# BM43112DC02_PIJIAKUN_SCH.net
KiCad netlist of a schematic drawn in Altium Designer
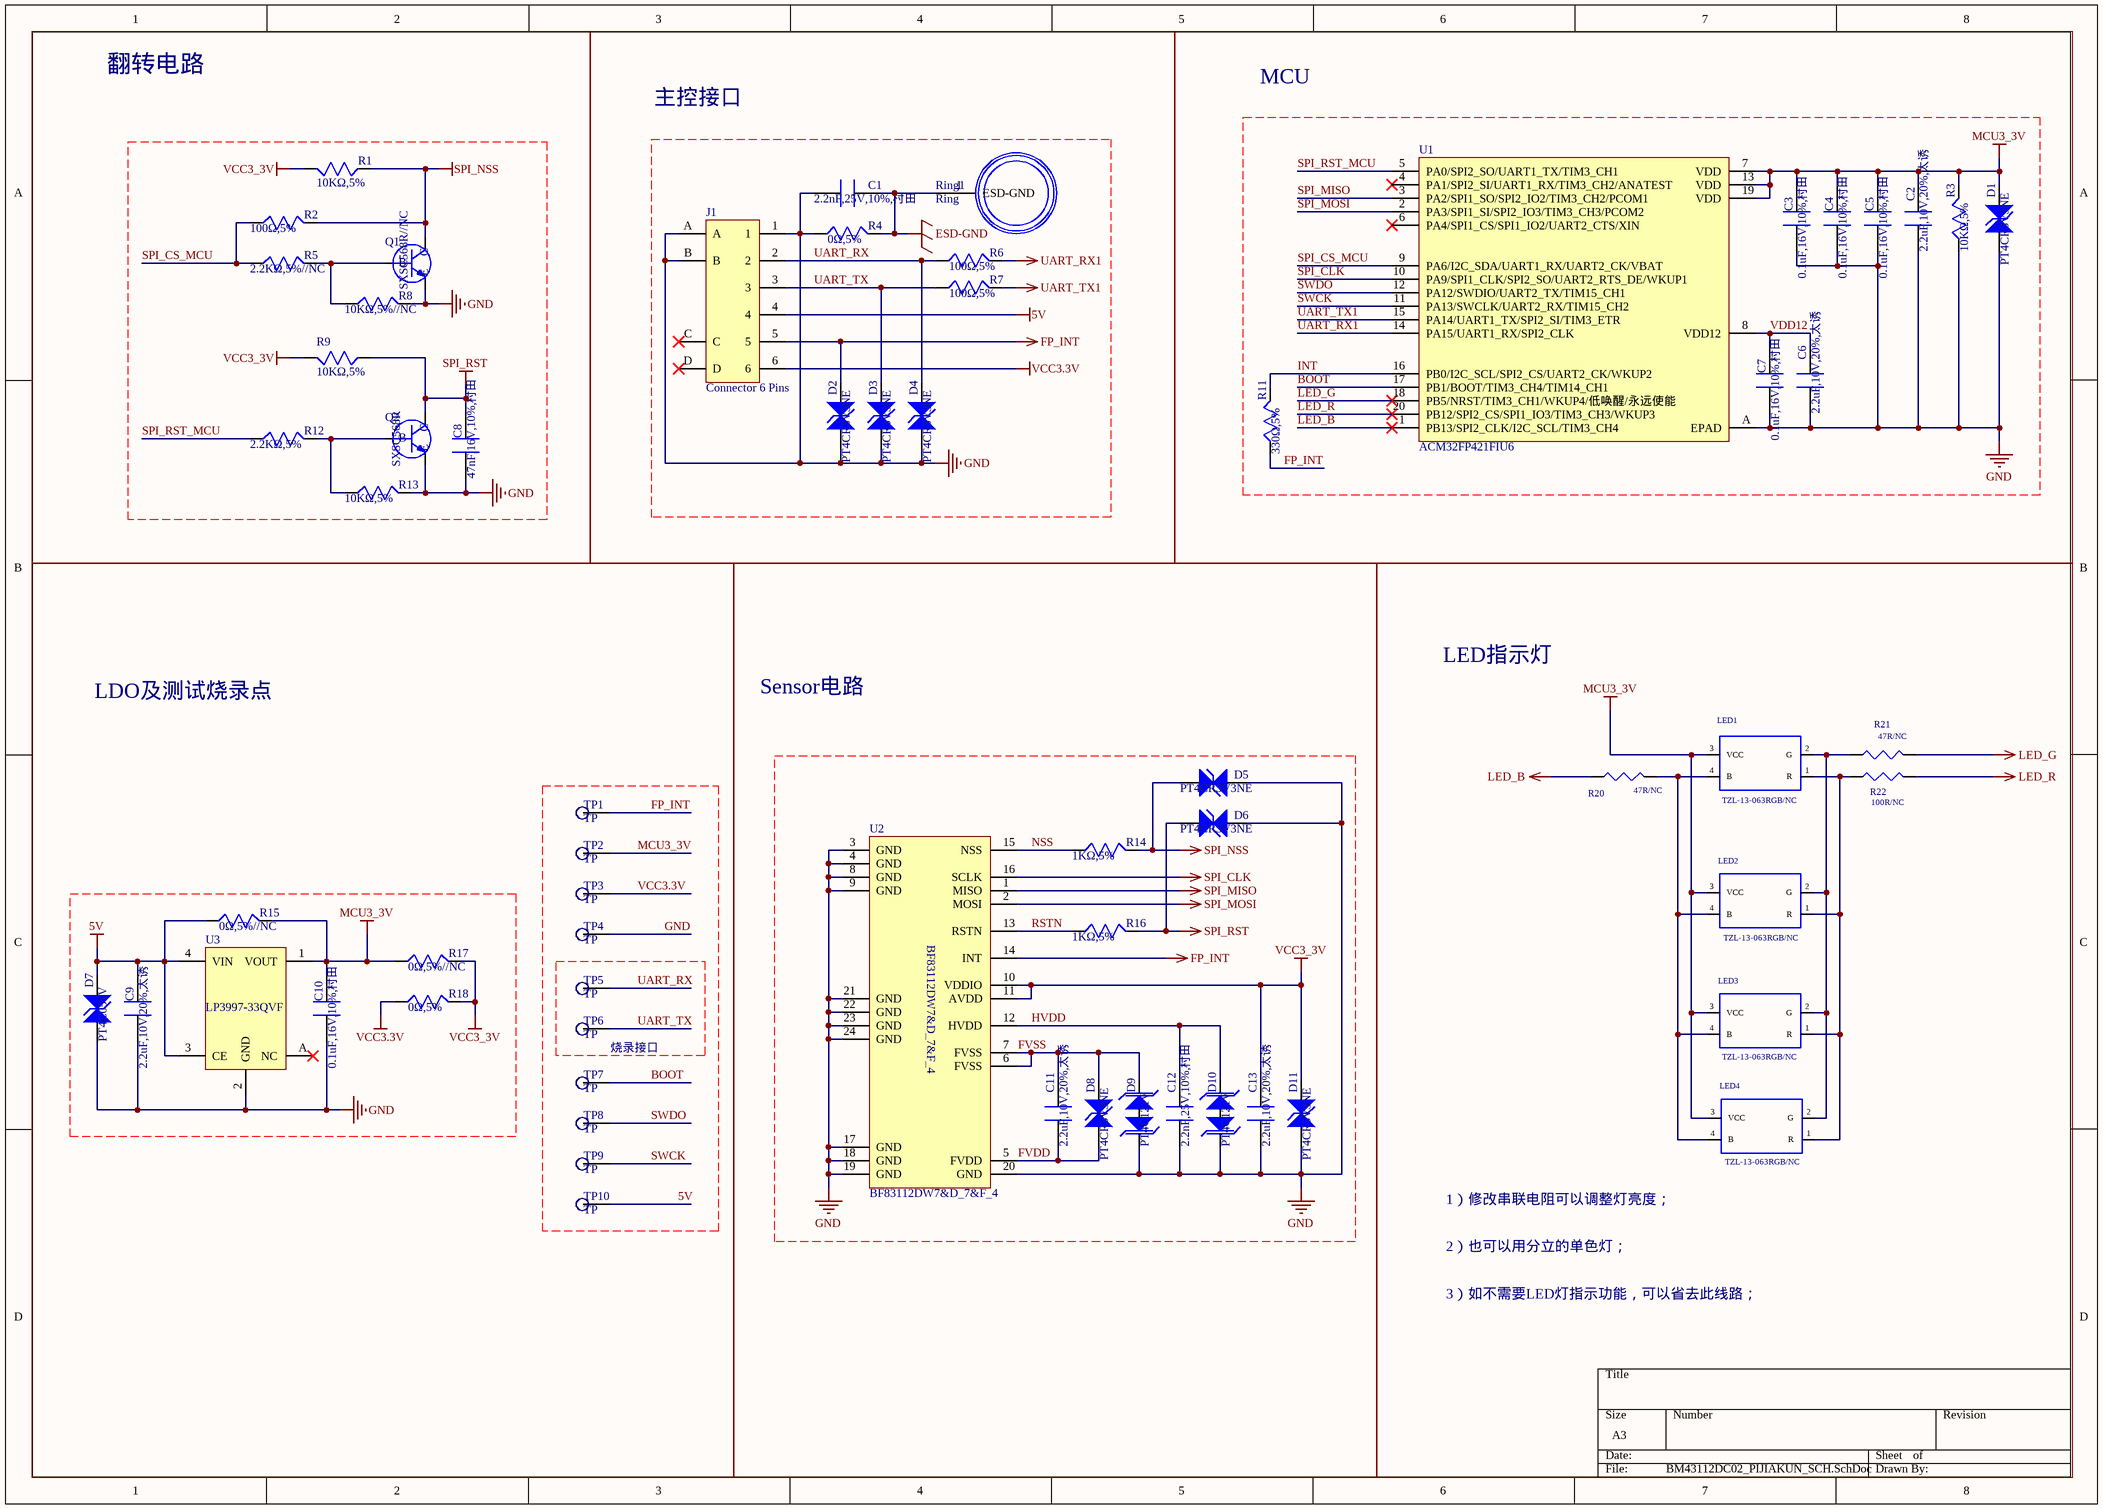
[diagram p0: BM43112DC02_PIJIAKUN_SCH.SchDoc]

(export (version "E")
  (design (tool "Eeschema 10.0.6"))
  (components
    (comp (ref "C1")
      (value "2.2nF,25V,10%,村田")
      (footprint "C0201")
      (description "贴片电容")
      (libsource (lib "Mkyou") (part "Cap"))
    )
    (comp (ref "C2")
      (value "2.2uF,10V,20%,太诱")
      (footprint "C0201")
      (description "贴片电容")
      (libsource (lib "Mkyou") (part "Cap"))
    )
    (comp (ref "C3")
      (value "0.1uF,16V,10%,村田")
      (footprint "C0201")
      (description "贴片电容")
      (libsource (lib "Mkyou") (part "Cap"))
    )
    (comp (ref "C4")
      (value "0.1uF,16V,10%,村田")
      (footprint "C0201")
      (description "贴片电容")
      (libsource (lib "Mkyou") (part "Cap"))
    )
    (comp (ref "C5")
      (value "0.1uF,16V,10%,村田")
      (footprint "C0201")
      (description "贴片电容")
      (libsource (lib "Mkyou") (part "Cap"))
    )
    (comp (ref "C6")
      (value "2.2uF,10V,20%,太诱")
      (footprint "C0201")
      (description "贴片电容")
      (libsource (lib "Mkyou") (part "Cap"))
    )
    (comp (ref "C7")
      (value "0.1uF,16V,10%,村田")
      (footprint "C0201")
      (description "贴片电容")
      (libsource (lib "Mkyou") (part "Cap"))
    )
    (comp (ref "C8")
      (value "47nF,16V,10%,村田")
      (footprint "C0201")
      (description "贴片电容")
      (libsource (lib "Mkyou") (part "Cap"))
    )
    (comp (ref "C9")
      (value "2.2uF,10V,20%,太诱")
      (footprint "C0201")
      (description "贴片电容")
      (libsource (lib "Mkyou") (part "Cap"))
    )
    (comp (ref "C10")
      (value "0.1uF,16V,10%,村田")
      (footprint "C0201")
      (description "贴片电容")
      (libsource (lib "Mkyou") (part "Cap"))
    )
    (comp (ref "C11")
      (value "2.2uF,10V,20%,太诱")
      (footprint "CC0402-M")
      (description "贴片电容")
      (libsource (lib "Mkyou") (part "Cap"))
    )
    (comp (ref "C12")
      (value "2.2nF,25V,10%,村田")
      (footprint "C0201")
      (description "贴片电容")
      (libsource (lib "Mkyou") (part "Cap"))
    )
    (comp (ref "C13")
      (value "2.2uF,10V,20%,太诱")
      (footprint "CC0402-M")
      (description "贴片电容")
      (libsource (lib "Mkyou") (part "Cap"))
    )
    (comp (ref "D1")
      (value "PT4CR3V3NE")
      (footprint "SOD-962")
      (description "双向静电二极管")
      (libsource (lib "Mkyou") (part "ESD"))
    )
    (comp (ref "D2")
      (value "PT4CR3V3NE")
      (footprint "SOD-962")
      (description "双向静电二极管")
      (libsource (lib "Mkyou") (part "ESD"))
    )
    (comp (ref "D3")
      (value "PT4CR3V3NE")
      (footprint "SOD-962")
      (description "双向静电二极管")
      (libsource (lib "Mkyou") (part "ESD"))
    )
    (comp (ref "D4")
      (value "PT4CR3V3NE")
      (footprint "SOD-962")
      (description "双向静电二极管")
      (libsource (lib "Mkyou") (part "ESD"))
    )
    (comp (ref "D5")
      (value "PT4CR3V3NE")
      (footprint "SOD-962")
      (description "双向静电二极管")
      (libsource (lib "Mkyou") (part "ESD"))
    )
    (comp (ref "D6")
      (value "PT4CR3V3NE")
      (footprint "SOD-962")
      (description "双向静电二极管")
      (libsource (lib "Mkyou") (part "ESD"))
    )
    (comp (ref "D7")
      (value "PT4C051V")
      (footprint "DFN0603-2L 0.3*0.23 Pitch 0.38")
      (description "双向静电二极管")
      (libsource (lib "Mkyou") (part "ESD"))
    )
    (comp (ref "D8")
      (value "PT4CR3V3NE")
      (footprint "SOD-962")
      (description "双向静电二极管")
      (libsource (lib "Mkyou") (part "ESD"))
    )
    (comp (ref "D9")
      (value "PT4C121V")
      (footprint "SOD-962")
      (description "双向瞬态抑制二极管")
      (libsource (lib "Mkyou") (part "TVS"))
    )
    (comp (ref "D10")
      (value "PT4C121V")
      (footprint "SOD-962")
      (description "双向瞬态抑制二极管")
      (libsource (lib "Mkyou") (part "TVS"))
    )
    (comp (ref "D11")
      (value "PT4CR3V3NE")
      (footprint "SOD-962")
      (description "双向静电二极管")
      (libsource (lib "Mkyou") (part "ESD"))
    )
    (comp (ref "J1")
      (value "Connector 6 Pins")
      (footprint "CON6_10")
      (description "连接器")
      (libsource (lib "Mkyou") (part "Connector 6 Pins"))
    )
    (comp (ref "LED1")
      (value "TZL-13-063RGB/NC")
      (footprint "S1615RGB")
      (libsource (lib "*") (part "TZL-13-063RGB"))
    )
    (comp (ref "LED2")
      (value "TZL-13-063RGB/NC")
      (footprint "S1615RGB")
      (libsource (lib "*") (part "TZL-13-063RGB"))
    )
    (comp (ref "LED3")
      (value "TZL-13-063RGB/NC")
      (footprint "S1615RGB")
      (libsource (lib "*") (part "TZL-13-063RGB"))
    )
    (comp (ref "LED4")
      (value "TZL-13-063RGB/NC")
      (footprint "S1615RGB")
      (libsource (lib "*") (part "TZL-13-063RGB"))
    )
    (comp (ref "Q1")
      (value "SXSC568R//NC")
      (footprint "SOT-723")
      (description "NPN型三极管")
      (libsource (lib "Mkyou") (part "NPN BCE"))
    )
    (comp (ref "Q2")
      (value "SXSC568R")
      (footprint "SOT-723")
      (description "NPN型三极管")
      (libsource (lib "Mkyou") (part "NPN BCE"))
    )
    (comp (ref "R1")
      (value "10KΩ,5%")
      (footprint "R0201")
      (description "贴片电阻")
      (libsource (lib "Mkyou") (part "RES"))
    )
    (comp (ref "R2")
      (value "100Ω,5%")
      (footprint "R0201")
      (description "贴片电阻")
      (libsource (lib "Mkyou") (part "RES"))
    )
    (comp (ref "R3")
      (value "10KΩ,5%")
      (footprint "R0201")
      (description "贴片电阻")
      (libsource (lib "Mkyou") (part "RES"))
    )
    (comp (ref "R4")
      (value "0Ω,5%")
      (footprint "R0201")
      (description "贴片电阻")
      (libsource (lib "Mkyou") (part "RES"))
    )
    (comp (ref "R5")
      (value "2.2KΩ,5%//NC")
      (footprint "R0201")
      (description "贴片电阻")
      (libsource (lib "Mkyou") (part "RES"))
    )
    (comp (ref "R6")
      (value "100Ω,5%")
      (footprint "R0201")
      (description "贴片电阻")
      (libsource (lib "Mkyou") (part "RES"))
    )
    (comp (ref "R7")
      (value "100Ω,5%")
      (footprint "R0201")
      (description "贴片电阻")
      (libsource (lib "Mkyou") (part "RES"))
    )
    (comp (ref "R8")
      (value "10KΩ,5%//NC")
      (footprint "R0201")
      (description "贴片电阻")
      (libsource (lib "Mkyou") (part "RES"))
    )
    (comp (ref "R9")
      (value "10KΩ,5%")
      (footprint "R0201")
      (description "贴片电阻")
      (libsource (lib "Mkyou") (part "RES"))
    )
    (comp (ref "R11")
      (value "330Ω,5%")
      (footprint "R0201")
      (description "贴片电阻")
      (libsource (lib "Mkyou") (part "RES"))
    )
    (comp (ref "R12")
      (value "2.2KΩ,5%")
      (footprint "R0201")
      (description "贴片电阻")
      (libsource (lib "Mkyou") (part "RES"))
    )
    (comp (ref "R13")
      (value "10KΩ,5%")
      (footprint "R0201")
      (description "贴片电阻")
      (libsource (lib "Mkyou") (part "RES"))
    )
    (comp (ref "R14")
      (value "1KΩ,5%")
      (footprint "R0201")
      (description "贴片电阻")
      (libsource (lib "Mkyou") (part "RES"))
    )
    (comp (ref "R15")
      (value "0Ω,5%//NC")
      (footprint "R0201")
      (description "贴片电阻")
      (libsource (lib "Mkyou") (part "RES"))
    )
    (comp (ref "R16")
      (value "1KΩ,5%")
      (footprint "R0201")
      (description "贴片电阻")
      (libsource (lib "Mkyou") (part "RES"))
    )
    (comp (ref "R17")
      (value "0Ω,5%//NC")
      (footprint "R0201")
      (description "贴片电阻")
      (libsource (lib "Mkyou") (part "RES"))
    )
    (comp (ref "R18")
      (value "0Ω,5%")
      (footprint "R0201")
      (description "贴片电阻")
      (libsource (lib "Mkyou") (part "RES"))
    )
    (comp (ref "R20")
      (value "47R/NC")
      (footprint "R0201")
      (description "RES S 0402 5.1Ω J 1/16W")
      (fields (field (name "PART_NUMBER") "3.0109.06100"))
      (libsource (lib "*") (part "R0201"))
    )
    (comp (ref "R21")
      (value "47R/NC")
      (footprint "R0201")
      (description "RES S 0402 5.1Ω J 1/16W")
      (fields (field (name "PART_NUMBER") "3.0109.06100"))
      (libsource (lib "*") (part "R0201"))
    )
    (comp (ref "R22")
      (value "100R/NC")
      (footprint "R0201")
      (description "RES S 0402 5.1Ω J 1/16W")
      (fields (field (name "PART_NUMBER") "3.0109.06100"))
      (libsource (lib "*") (part "R0201"))
    )
    (comp (ref "Ring1")
      (value "Ring")
      (footprint "Ring")
      (description "金属环")
      (libsource (lib "Mkyou") (part "Ring"))
    )
    (comp (ref "TP1")
      (value "TP")
      (footprint "TP（Φ0.5）")
      (description "非正常物料无需采购")
      (libsource (lib "Mkyou") (part "TP"))
    )
    (comp (ref "TP2")
      (value "TP")
      (footprint "TP（Φ0.5）")
      (description "非正常物料无需采购")
      (libsource (lib "Mkyou") (part "TP"))
    )
    (comp (ref "TP3")
      (value "TP")
      (footprint "TP（Φ0.5）")
      (description "非正常物料无需采购")
      (libsource (lib "Mkyou") (part "TP"))
    )
    (comp (ref "TP4")
      (value "TP")
      (footprint "TP（Φ0.5）")
      (description "非正常物料无需采购")
      (libsource (lib "Mkyou") (part "TP"))
    )
    (comp (ref "TP5")
      (value "TP")
      (footprint "TP（Φ0.5）")
      (description "非正常物料无需采购")
      (libsource (lib "Mkyou") (part "TP"))
    )
    (comp (ref "TP6")
      (value "TP")
      (footprint "TP（Φ0.5）")
      (description "非正常物料无需采购")
      (libsource (lib "Mkyou") (part "TP"))
    )
    (comp (ref "TP7")
      (value "TP")
      (footprint "TP（Φ0.5）")
      (description "非正常物料无需采购")
      (libsource (lib "Mkyou") (part "TP"))
    )
    (comp (ref "TP8")
      (value "TP")
      (footprint "TP（Φ0.5）")
      (description "非正常物料无需采购")
      (libsource (lib "Mkyou") (part "TP"))
    )
    (comp (ref "TP9")
      (value "TP")
      (footprint "TP（Φ0.5）")
      (description "非正常物料无需采购")
      (libsource (lib "Mkyou") (part "TP"))
    )
    (comp (ref "TP10")
      (value "TP")
      (footprint "TP（Φ0.5）")
      (description "非正常物料无需采购")
      (libsource (lib "Mkyou") (part "TP"))
    )
    (comp (ref "U1")
      (value "ACM32FP421FIU6")
      (footprint "QFN 20 3*3 Pitch 0.4")
      (description "微控制单元")
      (libsource (lib "Mkyou") (part "ACM32FP421"))
    )
    (comp (ref "U2")
      (value "BF83112DW7&D_7&F_4")
      (footprint "BF83112DW7&D_7&F_4")
      (description "电容按压式指纹识别芯片")
      (libsource (lib "Mkyou") (part "BF83112DW7&D_7&F_4"))
    )
    (comp (ref "U3")
      (value "LP3997-33QVF")
      (footprint "DFN 1*1-4L")
      (description "线性稳压器")
      (libsource (lib "Mkyou") (part "LDO 4 Pins"))
    )
  )
  (nets
    (net (code "1") (name "/BOOT") (class "Default")
      (node (ref "TP7") (pin "1") (pinfunction "1_1") (pintype "passive"))
      (node (ref "U1") (pin "17") (pinfunction "PB1/BOOT/TIM3_CH4/TIM14_CH1_17") (pintype "passive"))
    )
    (net (code "2") (name "/FVDD") (class "Default")
      (node (ref "C11") (pin "1") (pinfunction "1_1") (pintype "passive"))
      (node (ref "D8") (pin "1") (pinfunction "1_1") (pintype "passive"))
      (node (ref "U2") (pin "5") (pinfunction "FVDD_5") (pintype "passive"))
    )
    (net (code "3") (name "/FVSS") (class "Default")
      (node (ref "C11") (pin "2") (pinfunction "2_2") (pintype "passive"))
      (node (ref "D8") (pin "2") (pinfunction "2_2") (pintype "passive"))
      (node (ref "D9") (pin "1") (pinfunction "1_1") (pintype "passive"))
      (node (ref "U2") (pin "6") (pinfunction "FVSS_6") (pintype "passive"))
      (node (ref "U2") (pin "7") (pinfunction "FVSS_7") (pintype "passive"))
    )
    (net (code "4") (name "/HVDD") (class "Default")
      (node (ref "C12") (pin "2") (pinfunction "2_2") (pintype "passive"))
      (node (ref "D10") (pin "1") (pinfunction "1_1") (pintype "passive"))
      (node (ref "U2") (pin "12") (pinfunction "HVDD_12") (pintype "passive"))
    )
    (net (code "5") (name "/INT") (class "Default")
      (node (ref "R11") (pin "2") (pinfunction "2_2") (pintype "passive"))
      (node (ref "U1") (pin "16") (pinfunction "PB0/I2C_SCL/SPI2_CS/UART2_CK/WKUP2_16") (pintype "passive"))
    )
    (net (code "6") (name "/NSS") (class "Default")
      (node (ref "R14") (pin "1") (pinfunction "1_1") (pintype "passive"))
      (node (ref "U2") (pin "15") (pinfunction "NSS_15") (pintype "passive"))
    )
    (net (code "7") (name "/RSTN") (class "Default")
      (node (ref "R16") (pin "1") (pinfunction "1_1") (pintype "passive"))
      (node (ref "U2") (pin "13") (pinfunction "RSTN_13") (pintype "passive"))
    )
    (net (code "8") (name "/SPI_CS_MCU") (class "Default")
      (node (ref "R2") (pin "1") (pinfunction "1_1") (pintype "passive"))
      (node (ref "R5") (pin "1") (pinfunction "1_1") (pintype "passive"))
      (node (ref "U1") (pin "9") (pinfunction "PA6/I2C_SDA/UART1_RX/UART2_CK/VBAT_9") (pintype "passive"))
    )
    (net (code "9") (name "/SPI_RST_MCU") (class "Default")
      (node (ref "R12") (pin "1") (pinfunction "1_1") (pintype "passive"))
      (node (ref "U1") (pin "5") (pinfunction "PA0/SPI2_SO/UART1_TX/TIM3_CH1_5") (pintype "passive"))
    )
    (net (code "10") (name "/SWCK") (class "Default")
      (node (ref "TP9") (pin "1") (pinfunction "1_1") (pintype "passive"))
      (node (ref "U1") (pin "11") (pinfunction "PA13/SWCLK/UART2_RX/TIM15_CH2_11") (pintype "passive"))
    )
    (net (code "11") (name "/SWDO") (class "Default")
      (node (ref "TP8") (pin "1") (pinfunction "1_1") (pintype "passive"))
      (node (ref "U1") (pin "12") (pinfunction "PA12/SWDIO/UART2_TX/TIM15_CH1_12") (pintype "passive"))
    )
    (net (code "12") (name "/UART_RX") (class "Default")
      (node (ref "D4") (pin "2") (pinfunction "2_2") (pintype "passive"))
      (node (ref "J1") (pin "2") (pinfunction "2_2") (pintype "passive"))
      (node (ref "R6") (pin "1") (pinfunction "1_1") (pintype "passive"))
      (node (ref "TP5") (pin "1") (pinfunction "1_1") (pintype "passive"))
    )
    (net (code "13") (name "/UART_TX") (class "Default")
      (node (ref "D3") (pin "2") (pinfunction "2_2") (pintype "passive"))
      (node (ref "J1") (pin "3") (pinfunction "3_3") (pintype "passive"))
      (node (ref "R7") (pin "1") (pinfunction "1_1") (pintype "passive"))
      (node (ref "TP6") (pin "1") (pinfunction "1_1") (pintype "passive"))
    )
    (net (code "14") (name "/VDD12") (class "Default")
      (node (ref "C6") (pin "2") (pinfunction "2_2") (pintype "passive"))
      (node (ref "C7") (pin "2") (pinfunction "2_2") (pintype "passive"))
      (node (ref "U1") (pin "8") (pinfunction "VDD12_8") (pintype "passive"))
    )
    (net (code "15") (name "5V") (class "Default")
      (node (ref "C9") (pin "2") (pinfunction "2_2") (pintype "passive"))
      (node (ref "D7") (pin "2") (pinfunction "2_2") (pintype "passive"))
      (node (ref "J1") (pin "4") (pinfunction "4_4") (pintype "passive"))
      (node (ref "R15") (pin "1") (pinfunction "1_1") (pintype "passive"))
      (node (ref "TP10") (pin "1") (pinfunction "1_1") (pintype "passive"))
      (node (ref "U3") (pin "3") (pinfunction "CE_3") (pintype "passive"))
      (node (ref "U3") (pin "4") (pinfunction "VIN_4") (pintype "passive"))
    )
    (net (code "16") (name "ESD-GND") (class "Default")
      (node (ref "C1") (pin "1") (pinfunction "1_1") (pintype "passive"))
      (node (ref "R4") (pin "2") (pinfunction "2_2") (pintype "passive"))
      (node (ref "Ring1") (pin "1") (pinfunction "ESD-GND_1") (pintype "passive"))
    )
    (net (code "17") (name "FP_INT") (class "Default")
      (node (ref "D2") (pin "2") (pinfunction "2_2") (pintype "passive"))
      (node (ref "J1") (pin "5") (pinfunction "5_5") (pintype "passive"))
      (node (ref "R11") (pin "1") (pinfunction "1_1") (pintype "passive"))
      (node (ref "TP1") (pin "1") (pinfunction "1_1") (pintype "passive"))
      (node (ref "U2") (pin "14") (pinfunction "INT_14") (pintype "passive"))
    )
    (net (code "18") (name "GND") (class "Default")
      (node (ref "C1") (pin "2") (pinfunction "2_2") (pintype "passive"))
      (node (ref "C10") (pin "1") (pinfunction "1_1") (pintype "passive"))
      (node (ref "C12") (pin "1") (pinfunction "1_1") (pintype "passive"))
      (node (ref "C13") (pin "1") (pinfunction "1_1") (pintype "passive"))
      (node (ref "C2") (pin "1") (pinfunction "1_1") (pintype "passive"))
      (node (ref "C3") (pin "1") (pinfunction "1_1") (pintype "passive"))
      (node (ref "C4") (pin "1") (pinfunction "1_1") (pintype "passive"))
      (node (ref "C5") (pin "1") (pinfunction "1_1") (pintype "passive"))
      (node (ref "C6") (pin "1") (pinfunction "1_1") (pintype "passive"))
      (node (ref "C7") (pin "1") (pinfunction "1_1") (pintype "passive"))
      (node (ref "C8") (pin "1") (pinfunction "1_1") (pintype "passive"))
      (node (ref "C9") (pin "1") (pinfunction "1_1") (pintype "passive"))
      (node (ref "D1") (pin "1") (pinfunction "1_1") (pintype "passive"))
      (node (ref "D10") (pin "2") (pinfunction "2_2") (pintype "passive"))
      (node (ref "D11") (pin "1") (pinfunction "1_1") (pintype "passive"))
      (node (ref "D2") (pin "1") (pinfunction "1_1") (pintype "passive"))
      (node (ref "D3") (pin "1") (pinfunction "1_1") (pintype "passive"))
      (node (ref "D4") (pin "1") (pinfunction "1_1") (pintype "passive"))
      (node (ref "D5") (pin "1") (pinfunction "1_1") (pintype "passive"))
      (node (ref "D6") (pin "1") (pinfunction "1_1") (pintype "passive"))
      (node (ref "D7") (pin "1") (pinfunction "1_1") (pintype "passive"))
      (node (ref "D9") (pin "2") (pinfunction "2_2") (pintype "passive"))
      (node (ref "J1") (pin "1") (pinfunction "1_1") (pintype "passive"))
      (node (ref "J1") (pin "A") (pinfunction "A_A") (pintype "passive"))
      (node (ref "J1") (pin "B") (pinfunction "B_B") (pintype "passive"))
      (node (ref "Q1") (pin "2") (pinfunction "E_2") (pintype "passive"))
      (node (ref "Q2") (pin "2") (pinfunction "E_2") (pintype "passive"))
      (node (ref "R13") (pin "2") (pinfunction "2_2") (pintype "passive"))
      (node (ref "R3") (pin "1") (pinfunction "1_1") (pintype "passive"))
      (node (ref "R4") (pin "1") (pinfunction "1_1") (pintype "passive"))
      (node (ref "R8") (pin "2") (pinfunction "2_2") (pintype "passive"))
      (node (ref "TP4") (pin "1") (pinfunction "1_1") (pintype "passive"))
      (node (ref "U1") (pin "A") (pinfunction "EPAD_A") (pintype "passive"))
      (node (ref "U2") (pin "17") (pinfunction "GND_17") (pintype "passive"))
      (node (ref "U2") (pin "18") (pinfunction "GND_18") (pintype "passive"))
      (node (ref "U2") (pin "19") (pinfunction "GND_19") (pintype "passive"))
      (node (ref "U2") (pin "20") (pinfunction "GND_20") (pintype "passive"))
      (node (ref "U2") (pin "21") (pinfunction "GND_21") (pintype "passive"))
      (node (ref "U2") (pin "22") (pinfunction "GND_22") (pintype "passive"))
      (node (ref "U2") (pin "23") (pinfunction "GND_23") (pintype "passive"))
      (node (ref "U2") (pin "24") (pinfunction "GND_24") (pintype "passive"))
      (node (ref "U2") (pin "3") (pinfunction "GND_3") (pintype "passive"))
      (node (ref "U2") (pin "4") (pinfunction "GND_4") (pintype "passive"))
      (node (ref "U2") (pin "8") (pinfunction "GND_8") (pintype "passive"))
      (node (ref "U2") (pin "9") (pinfunction "GND_9") (pintype "passive"))
      (node (ref "U3") (pin "2") (pinfunction "GND_2") (pintype "passive"))
    )
    (net (code "19") (name "LED_B") (class "Default")
      (node (ref "R20") (pin "1") (pinfunction "1_1") (pintype "passive"))
      (node (ref "U1") (pin "1") (pinfunction "PB13/SPI2_CLK/I2C_SCL/TIM3_CH4_1") (pintype "passive"))
    )
    (net (code "20") (name "LED_G") (class "Default")
      (node (ref "R21") (pin "2") (pinfunction "2_2") (pintype "passive"))
      (node (ref "U1") (pin "18") (pinfunction "PB5/NRST/TIM3_CH1/WKUP4/低唤醒/永远使能_18") (pintype "passive"))
    )
    (net (code "21") (name "LED_R") (class "Default")
      (node (ref "R22") (pin "2") (pinfunction "2_2") (pintype "passive"))
      (node (ref "U1") (pin "20") (pinfunction "PB12/SPI2_CS/SPI1_IO3/TIM3_CH3/WKUP3_20") (pintype "passive"))
    )
    (net (code "22") (name "MCU3_3V") (class "Default")
      (node (ref "C10") (pin "2") (pinfunction "2_2") (pintype "passive"))
      (node (ref "C2") (pin "2") (pinfunction "2_2") (pintype "passive"))
      (node (ref "C3") (pin "2") (pinfunction "2_2") (pintype "passive"))
      (node (ref "C4") (pin "2") (pinfunction "2_2") (pintype "passive"))
      (node (ref "C5") (pin "2") (pinfunction "2_2") (pintype "passive"))
      (node (ref "D1") (pin "2") (pinfunction "2_2") (pintype "passive"))
      (node (ref "LED1") (pin "3") (pinfunction "VCC_3") (pintype "passive"))
      (node (ref "LED2") (pin "3") (pinfunction "VCC_3") (pintype "passive"))
      (node (ref "LED3") (pin "3") (pinfunction "VCC_3") (pintype "passive"))
      (node (ref "LED4") (pin "3") (pinfunction "VCC_3") (pintype "passive"))
      (node (ref "R15") (pin "2") (pinfunction "2_2") (pintype "passive"))
      (node (ref "R17") (pin "1") (pinfunction "1_1") (pintype "passive"))
      (node (ref "R3") (pin "2") (pinfunction "2_2") (pintype "passive"))
      (node (ref "TP2") (pin "1") (pinfunction "1_1") (pintype "passive"))
      (node (ref "U1") (pin "13") (pinfunction "VDD_13") (pintype "passive"))
      (node (ref "U1") (pin "19") (pinfunction "VDD_19") (pintype "passive"))
      (node (ref "U1") (pin "7") (pinfunction "VDD_7") (pintype "passive"))
      (node (ref "U3") (pin "1") (pinfunction "VOUT_1") (pintype "passive"))
    )
    (net (code "23") (name "Net-(LED1-B)") (class "Default")
      (node (ref "LED1") (pin "4") (pinfunction "B_4") (pintype "passive"))
      (node (ref "LED2") (pin "4") (pinfunction "B_4") (pintype "passive"))
      (node (ref "LED3") (pin "4") (pinfunction "B_4") (pintype "passive"))
      (node (ref "LED4") (pin "4") (pinfunction "B_4") (pintype "passive"))
      (node (ref "R20") (pin "2") (pinfunction "2_2") (pintype "passive"))
    )
    (net (code "24") (name "Net-(LED1-G)") (class "Default")
      (node (ref "LED1") (pin "2") (pinfunction "G_2") (pintype "passive"))
      (node (ref "LED2") (pin "2") (pinfunction "G_2") (pintype "passive"))
      (node (ref "LED3") (pin "2") (pinfunction "G_2") (pintype "passive"))
      (node (ref "LED4") (pin "2") (pinfunction "G_2") (pintype "passive"))
      (node (ref "R21") (pin "1") (pinfunction "1_1") (pintype "passive"))
    )
    (net (code "25") (name "Net-(LED1-R)") (class "Default")
      (node (ref "LED1") (pin "1") (pinfunction "R_1") (pintype "passive"))
      (node (ref "LED2") (pin "1") (pinfunction "R_1") (pintype "passive"))
      (node (ref "LED3") (pin "1") (pinfunction "R_1") (pintype "passive"))
      (node (ref "LED4") (pin "1") (pinfunction "R_1") (pintype "passive"))
      (node (ref "R22") (pin "1") (pinfunction "1_1") (pintype "passive"))
    )
    (net (code "26") (name "Net-(Q1-B)") (class "Default")
      (node (ref "Q1") (pin "1") (pinfunction "B_1") (pintype "passive"))
      (node (ref "R5") (pin "2") (pinfunction "2_2") (pintype "passive"))
      (node (ref "R8") (pin "1") (pinfunction "1_1") (pintype "passive"))
    )
    (net (code "27") (name "Net-(Q2-B)") (class "Default")
      (node (ref "Q2") (pin "1") (pinfunction "B_1") (pintype "passive"))
      (node (ref "R12") (pin "2") (pinfunction "2_2") (pintype "passive"))
      (node (ref "R13") (pin "1") (pinfunction "1_1") (pintype "passive"))
    )
    (net (code "28") (name "SPI_CLK") (class "Default")
      (node (ref "U1") (pin "10") (pinfunction "PA9/SPI1_CLK/SPI2_SO/UART2_RTS_DE/WKUP1_10") (pintype "passive"))
      (node (ref "U2") (pin "16") (pinfunction "SCLK_16") (pintype "passive"))
    )
    (net (code "29") (name "SPI_MISO") (class "Default")
      (node (ref "U1") (pin "3") (pinfunction "PA2/SPI1_SO/SPI2_IO2/TIM3_CH2/PCOM1_3") (pintype "passive"))
      (node (ref "U2") (pin "1") (pinfunction "MISO_1") (pintype "passive"))
    )
    (net (code "30") (name "SPI_MOSI") (class "Default")
      (node (ref "U1") (pin "2") (pinfunction "PA3/SPI1_SI/SPI2_IO3/TIM3_CH3/PCOM2_2") (pintype "passive"))
      (node (ref "U2") (pin "2") (pinfunction "MOSI_2") (pintype "passive"))
    )
    (net (code "31") (name "SPI_NSS") (class "Default")
      (node (ref "D5") (pin "2") (pinfunction "2_2") (pintype "passive"))
      (node (ref "Q1") (pin "3") (pinfunction "C_3") (pintype "passive"))
      (node (ref "R1") (pin "1") (pinfunction "1_1") (pintype "passive"))
      (node (ref "R14") (pin "2") (pinfunction "2_2") (pintype "passive"))
      (node (ref "R2") (pin "2") (pinfunction "2_2") (pintype "passive"))
    )
    (net (code "32") (name "SPI_RST") (class "Default")
      (node (ref "C8") (pin "2") (pinfunction "2_2") (pintype "passive"))
      (node (ref "D6") (pin "2") (pinfunction "2_2") (pintype "passive"))
      (node (ref "Q2") (pin "3") (pinfunction "C_3") (pintype "passive"))
      (node (ref "R16") (pin "2") (pinfunction "2_2") (pintype "passive"))
      (node (ref "R9") (pin "1") (pinfunction "1_1") (pintype "passive"))
    )
    (net (code "33") (name "UART_RX1") (class "Default")
      (node (ref "R6") (pin "2") (pinfunction "2_2") (pintype "passive"))
      (node (ref "U1") (pin "14") (pinfunction "PA15/UART1_RX/SPI2_CLK_14") (pintype "passive"))
    )
    (net (code "34") (name "UART_TX1") (class "Default")
      (node (ref "R7") (pin "2") (pinfunction "2_2") (pintype "passive"))
      (node (ref "U1") (pin "15") (pinfunction "PA14/UART1_TX/SPI2_SI/TIM3_ETR_15") (pintype "passive"))
    )
    (net (code "35") (name "VCC3.3V") (class "Default")
      (node (ref "J1") (pin "6") (pinfunction "6_6") (pintype "passive"))
      (node (ref "R18") (pin "1") (pinfunction "1_1") (pintype "passive"))
      (node (ref "TP3") (pin "1") (pinfunction "1_1") (pintype "passive"))
    )
    (net (code "36") (name "VCC3_3V") (class "Default")
      (node (ref "C13") (pin "2") (pinfunction "2_2") (pintype "passive"))
      (node (ref "D11") (pin "2") (pinfunction "2_2") (pintype "passive"))
      (node (ref "R1") (pin "2") (pinfunction "2_2") (pintype "passive"))
      (node (ref "R17") (pin "2") (pinfunction "2_2") (pintype "passive"))
      (node (ref "R18") (pin "2") (pinfunction "2_2") (pintype "passive"))
      (node (ref "R9") (pin "2") (pinfunction "2_2") (pintype "passive"))
      (node (ref "U2") (pin "10") (pinfunction "VDDIO_10") (pintype "passive"))
      (node (ref "U2") (pin "11") (pinfunction "AVDD_11") (pintype "passive"))
    )
    (net (code "37") (name "unconnected-(J1-PadC)") (class "Default")
      (node (ref "J1") (pin "C") (pinfunction "C_C") (pintype "passive+no_connect"))
    )
    (net (code "38") (name "unconnected-(J1-PadD)") (class "Default")
      (node (ref "J1") (pin "D") (pinfunction "D_D") (pintype "passive+no_connect"))
    )
    (net (code "39") (name "unconnected-(U1-PA1{slash}SPI2_SI{slash}UART1_RX{slash}TIM3_CH2{slash}ANATEST-Pad4)") (class "Default")
      (node (ref "U1") (pin "4") (pinfunction "PA1/SPI2_SI/UART1_RX/TIM3_CH2/ANATEST_4") (pintype "passive+no_connect"))
    )
    (net (code "40") (name "unconnected-(U1-PA4{slash}SPI1_CS{slash}SPI1_IO2{slash}UART2_CTS{slash}XIN-Pad6)") (class "Default")
      (node (ref "U1") (pin "6") (pinfunction "PA4/SPI1_CS/SPI1_IO2/UART2_CTS/XIN_6") (pintype "passive+no_connect"))
    )
    (net (code "41") (name "unconnected-(U3-NC-PadA)") (class "Default")
      (node (ref "U3") (pin "A") (pinfunction "NC_A") (pintype "passive+no_connect"))
    )
  )
)
